# Nguyen_Ly.net
KiCad netlist of a schematic drawn in Altium Designer
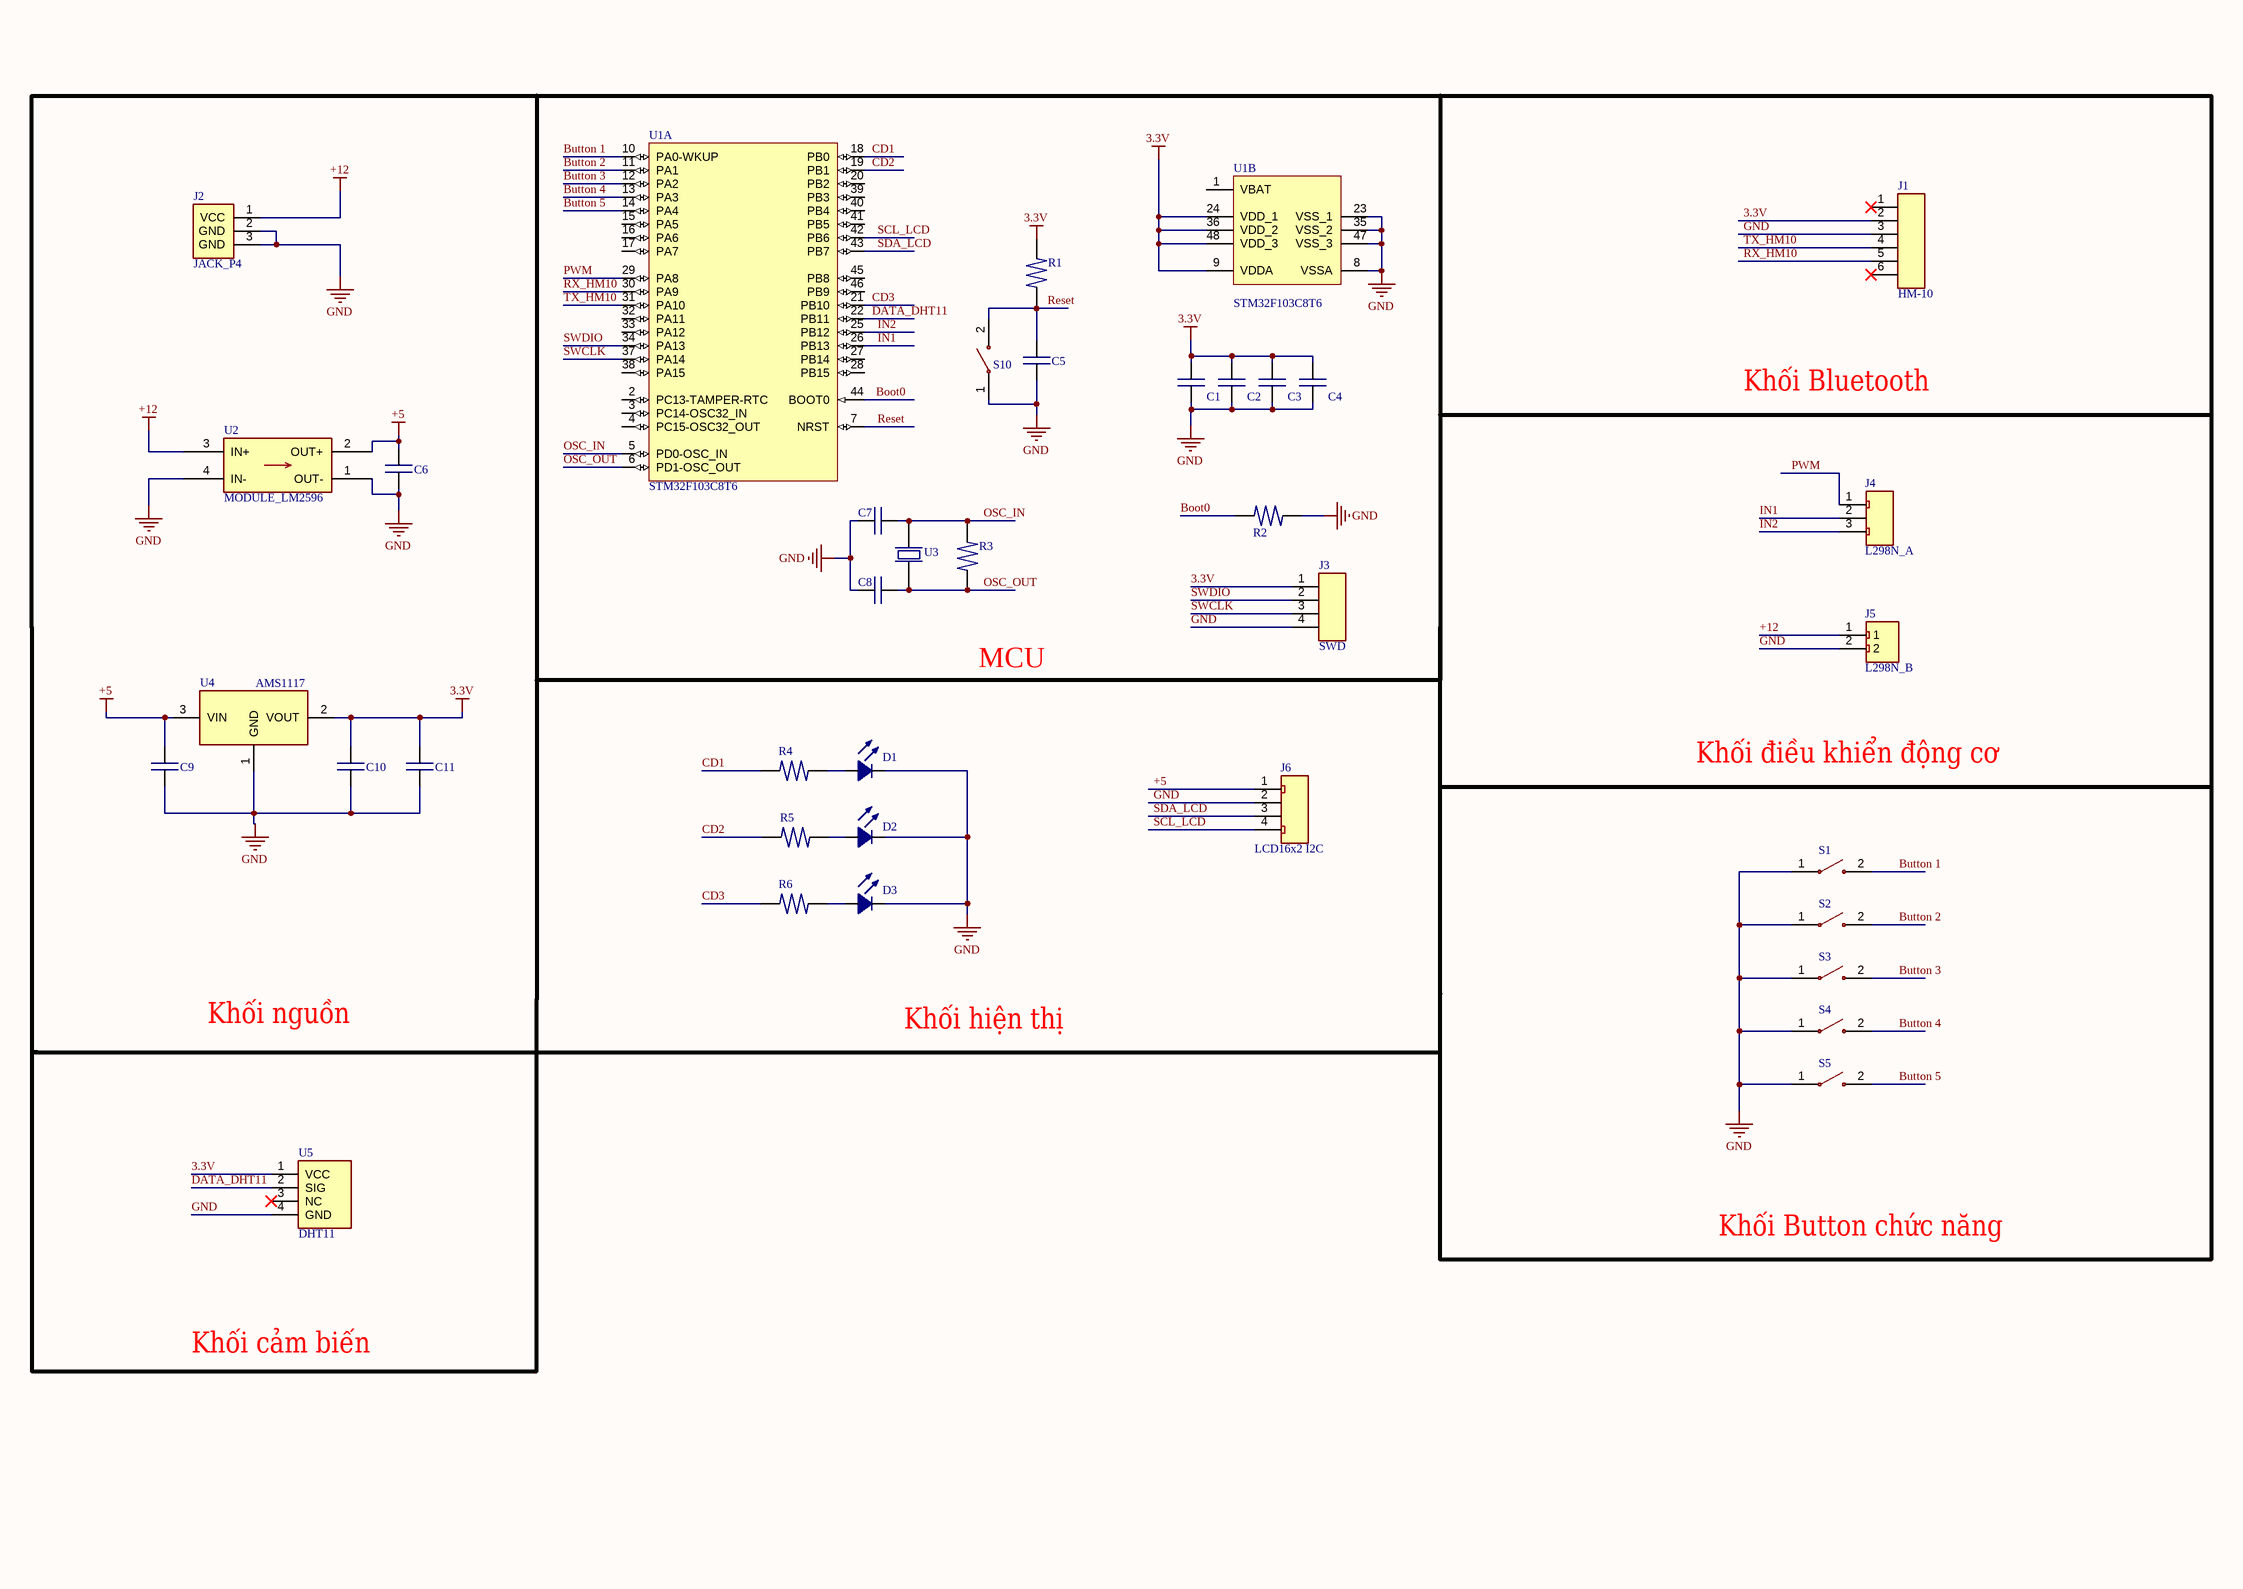
[diagram p0: Nguyen_Ly.SchDoc]

(export (version "E")
  (design (tool "Eeschema 10.0.6"))
  (components
    (comp (ref "C1")
      (value "CAPACITOR 0603")
      (footprint "CAPACITOR 0603")
      (description "Generic Capacitor 0603, 1.6x0.8x0.9mm.")
      (libsource (lib "MyComponents") (part "CAPACITOR 0603"))
    )
    (comp (ref "C2")
      (value "CAPACITOR 0603")
      (footprint "CAPACITOR 0603")
      (description "Generic Capacitor 0603, 1.6x0.8x0.9mm.")
      (libsource (lib "MyComponents") (part "CAPACITOR 0603"))
    )
    (comp (ref "C3")
      (value "CAPACITOR 0603")
      (footprint "CAPACITOR 0603")
      (description "Generic Capacitor 0603, 1.6x0.8x0.9mm.")
      (libsource (lib "MyComponents") (part "CAPACITOR 0603"))
    )
    (comp (ref "C4")
      (value "CAPACITOR 0603")
      (footprint "CAPACITOR 0603")
      (description "Generic Capacitor 0603, 1.6x0.8x0.9mm.")
      (libsource (lib "MyComponents") (part "CAPACITOR 0603"))
    )
    (comp (ref "C5")
      (value "CAPCITOR 104")
      (footprint "CAPACITOR 104")
      (description "Ceramic Capacitor 104, 3mm.")
      (libsource (lib "MyComponents") (part "CAPACITOR 104"))
    )
    (comp (ref "C6")
      (value "CAPCITOR 104")
      (footprint "CAPACITOR 104")
      (description "Ceramic Capacitor 104, 3mm.")
      (libsource (lib "MyComponents") (part "CAPACITOR 104"))
    )
    (comp (ref "C7")
      (value "CAPACITOR 0603")
      (footprint "CAPACITOR 0603")
      (description "Generic Capacitor 0603, 1.6x0.8x0.9mm.")
      (libsource (lib "MyComponents") (part "CAPACITOR 0603"))
    )
    (comp (ref "C8")
      (value "CAPACITOR 0603")
      (footprint "CAPACITOR 0603")
      (description "Generic Capacitor 0603, 1.6x0.8x0.9mm.")
      (libsource (lib "MyComponents") (part "CAPACITOR 0603"))
    )
    (comp (ref "C9")
      (value "CAPACITOR 0603")
      (footprint "CAPACITOR 0603")
      (description "Generic Capacitor 0603, 1.6x0.8x0.9mm.")
      (libsource (lib "MyComponents") (part "CAPACITOR 0603"))
    )
    (comp (ref "C10")
      (value "CAPACITOR 0603")
      (footprint "CAPACITOR 0603")
      (description "Generic Capacitor 0603, 1.6x0.8x0.9mm.")
      (libsource (lib "MyComponents") (part "CAPACITOR 0603"))
    )
    (comp (ref "C11")
      (value "CAPACITOR 0603")
      (footprint "CAPACITOR 0603")
      (description "Generic Capacitor 0603, 1.6x0.8x0.9mm.")
      (libsource (lib "MyComponents") (part "CAPACITOR 0603"))
    )
    (comp (ref "D1")
      (value "LED_5mm_GREEN")
      (footprint "LED_5mm_GREEN")
      (description "LED PTH 5mm Green.")
      (libsource (lib "MyComponents") (part "LED_5mm_GREEN"))
    )
    (comp (ref "D2")
      (value "LED_5mm_YELLOW")
      (footprint "LED_5mm_YELLOW")
      (description "LED PTH 5mm Yellow.")
      (libsource (lib "MyComponents") (part "LED_5mm_YELLOW"))
    )
    (comp (ref "D3")
      (value "LED_5mm_RED")
      (footprint "LED_5mm_RED")
      (description "LED PTH 5mm Red.")
      (libsource (lib "MyComponents") (part "LED_5mm_RED"))
    )
    (comp (ref "J1")
      (value "HM-10")
      (footprint "FEMALE-2.54-6P")
      (description "Female Header Connector 2.54mm 6 Pins.")
      (libsource (lib "MyComponents") (part "FEMALE-2.54-6P"))
    )
    (comp (ref "J2")
      (value "JACK_P4")
      (footprint "JACK_P4")
      (description "9V Battery Connector Jack P4.")
      (libsource (lib "MyComponents") (part "JACK_P4"))
    )
    (comp (ref "J3")
      (value "SWD")
      (footprint "MALE-2.54-4P")
      (description "Male Header Connector 2.54mm 4 Pins.")
      (libsource (lib "MyComponents") (part "MALE-2.54-4P"))
    )
    (comp (ref "J4")
      (value "L298N_A")
      (footprint "JST-2.54-3P")
      (description "Female Connector JST 3 Vias, 2.54mm.")
      (libsource (lib "MyComponents") (part "JST-2.54-3P"))
    )
    (comp (ref "J5")
      (value "L298N_B")
      (footprint "BORNE-5.00-2P")
      (description "Borne 2 Vias, Pitch 5mm.")
      (libsource (lib "MyComponents") (part "BORNE-5.00-2P"))
    )
    (comp (ref "J6")
      (value "LCD16x2 I2C")
      (footprint "JST-2.54-4P")
      (description "Female Connector JST 4 Vias, 2.54mm.")
      (libsource (lib "MyComponents") (part "JST-2.54-4P"))
    )
    (comp (ref "R1")
      (value "RESISTOR_9.5mm")
      (footprint "RESISTOR_PTH_9.5mm")
      (description "Generic Resistor 9.5mm.")
      (libsource (lib "MyComponents") (part "RESISTOR_9.5mm"))
    )
    (comp (ref "R2")
      (value "RESISTOR_0603")
      (footprint "RESISTOR_0603")
      (description "Generic Resistor 0603.")
      (libsource (lib "MyComponents") (part "RESISTOR_0603"))
    )
    (comp (ref "R3")
      (value "RESISTOR_0603")
      (footprint "RESISTOR_0603")
      (description "Generic Resistor 0603.")
      (libsource (lib "MyComponents") (part "RESISTOR_0603"))
    )
    (comp (ref "R4")
      (value "RESISTOR_9.5mm")
      (footprint "RESISTOR_PTH_9.5mm")
      (description "Generic Resistor 9.5mm.")
      (libsource (lib "MyComponents") (part "RESISTOR_9.5mm"))
    )
    (comp (ref "R5")
      (value "RESISTOR_9.5mm")
      (footprint "RESISTOR_PTH_9.5mm")
      (description "Generic Resistor 9.5mm.")
      (libsource (lib "MyComponents") (part "RESISTOR_9.5mm"))
    )
    (comp (ref "R6")
      (value "RESISTOR_9.5mm")
      (footprint "RESISTOR_PTH_9.5mm")
      (description "Generic Resistor 9.5mm.")
      (libsource (lib "MyComponents") (part "RESISTOR_9.5mm"))
    )
    (comp (ref "S1")
      (value "PUSH_BUTTON_6X6")
      (footprint "PUSH_BUTTON_6X6")
      (description "Push Button Tactile Switch PTH 4 Pins 6x6mm.")
      (libsource (lib "") (part "PUSH_BUTTON_6X6_1"))
    )
    (comp (ref "S2")
      (value "PUSH_BUTTON_6X6")
      (footprint "PUSH_BUTTON_6X6")
      (description "Push Button Tactile Switch PTH 4 Pins 6x6mm.")
      (libsource (lib "") (part "PUSH_BUTTON_6X6_1"))
    )
    (comp (ref "S3")
      (value "PUSH_BUTTON_6X6")
      (footprint "PUSH_BUTTON_6X6")
      (description "Push Button Tactile Switch PTH 4 Pins 6x6mm.")
      (libsource (lib "") (part "PUSH_BUTTON_6X6_1"))
    )
    (comp (ref "S4")
      (value "PUSH_BUTTON_6X6")
      (footprint "PUSH_BUTTON_6X6")
      (description "Push Button Tactile Switch PTH 4 Pins 6x6mm.")
      (libsource (lib "") (part "PUSH_BUTTON_6X6_1"))
    )
    (comp (ref "S5")
      (value "PUSH_BUTTON_6X6")
      (footprint "PUSH_BUTTON_6X6")
      (description "Push Button Tactile Switch PTH 4 Pins 6x6mm.")
      (libsource (lib "") (part "PUSH_BUTTON_6X6_1"))
    )
    (comp (ref "S10")
      (value "PUSH_BUTTON_6X6")
      (footprint "PUSH_BUTTON_6X6")
      (description "Push Button Tactile Switch PTH 4 Pins 6x6mm.")
      (libsource (lib "MyComponents") (part "PUSH_BUTTON_6X6"))
    )
    (comp (ref "U1")
      (value "STM32F103C8T6")
      (footprint "STM-LQFP48_N")
      (libsource (lib "STMicroelectronics STM32 F1") (part "STM32F103C8T6"))
    )
    (comp (ref "U2")
      (value "MODULE_LM2596")
      (footprint "MODULE_LM2596")
      (description "MODULE BUCK STEP DOWN 3A 43x20mm")
      (libsource (lib "MyComponents") (part "MODULE_LM2596"))
    )
    (comp (ref "U3")
      (value "CRISTAL_16Mhz")
      (footprint "CRISTAL_16Mhz_SMD")
      (description "CRYSTAL 16MHZ, PTH and SMD")
      (libsource (lib "MyComponents") (part "CRISTAL_16Mhz"))
    )
    (comp (ref "U4")
      (value "AMS1117")
      (footprint "AMS1117")
      (description "IC REG LINEAR 1A SOT-89-3L")
      (libsource (lib "MyComponents") (part "AMS1117"))
    )
    (comp (ref "U5")
      (value "DHT11")
      (footprint "DHT11")
      (description "SENSOR HUMIDITY/TEMPERATURE")
      (libsource (lib "MyComponents") (part "DHT11"))
    )
  )
  (nets
    (net (code "1") (name "+5") (class "Default")
      (node (ref "C6") (pin "2") (pinfunction "2_2") (pintype "passive"))
      (node (ref "C9") (pin "2") (pinfunction "2_2") (pintype "passive"))
      (node (ref "J6") (pin "1") (pintype "passive"))
      (node (ref "U2") (pin "2") (pinfunction "OUT+_2") (pintype "passive"))
      (node (ref "U4") (pin "3") (pinfunction "VIN_3") (pintype "passive"))
    )
    (net (code "2") (name "+12") (class "Default")
      (node (ref "J2") (pin "1") (pinfunction "VCC_1") (pintype "passive"))
      (node (ref "J5") (pin "1") (pinfunction "1_1") (pintype "passive"))
      (node (ref "U2") (pin "3") (pinfunction "IN+_3") (pintype "passive"))
    )
    (net (code "3") (name "/Boot0") (class "Default")
      (node (ref "R2") (pin "2") (pinfunction "2_2") (pintype "passive"))
      (node (ref "U1") (pin "44") (pinfunction "BOOT0_44") (pintype "input"))
    )
    (net (code "4") (name "/Button 1") (class "Default")
      (node (ref "S1") (pin "2") (pinfunction "2_2") (pintype "passive"))
      (node (ref "U1") (pin "10") (pinfunction "PA0-WKUP_10") (pintype "bidirectional"))
    )
    (net (code "5") (name "/Button 2") (class "Default")
      (node (ref "S2") (pin "2") (pinfunction "2_2") (pintype "passive"))
      (node (ref "U1") (pin "11") (pinfunction "PA1_11") (pintype "bidirectional"))
    )
    (net (code "6") (name "/Button 3") (class "Default")
      (node (ref "S3") (pin "2") (pinfunction "2_2") (pintype "passive"))
      (node (ref "U1") (pin "12") (pinfunction "PA2_12") (pintype "bidirectional"))
    )
    (net (code "7") (name "/Button 4") (class "Default")
      (node (ref "S4") (pin "2") (pinfunction "2_2") (pintype "passive"))
      (node (ref "U1") (pin "13") (pinfunction "PA3_13") (pintype "bidirectional"))
    )
    (net (code "8") (name "/Button 5") (class "Default")
      (node (ref "S5") (pin "2") (pinfunction "2_2") (pintype "passive"))
      (node (ref "U1") (pin "14") (pinfunction "PA4_14") (pintype "bidirectional"))
    )
    (net (code "9") (name "/CD1") (class "Default")
      (node (ref "R4") (pin "1") (pinfunction "1_1") (pintype "passive"))
      (node (ref "U1") (pin "18") (pinfunction "PB0_18") (pintype "bidirectional"))
    )
    (net (code "10") (name "/CD2") (class "Default")
      (node (ref "R5") (pin "1") (pinfunction "1_1") (pintype "passive"))
      (node (ref "U1") (pin "19") (pinfunction "PB1_19") (pintype "bidirectional"))
    )
    (net (code "11") (name "/CD3") (class "Default")
      (node (ref "R6") (pin "1") (pinfunction "1_1") (pintype "passive"))
      (node (ref "U1") (pin "21") (pinfunction "PB10_21") (pintype "bidirectional"))
    )
    (net (code "12") (name "/DATA_DHT11") (class "Default")
      (node (ref "U1") (pin "22") (pinfunction "PB11_22") (pintype "bidirectional"))
      (node (ref "U5") (pin "2") (pinfunction "SIG_2") (pintype "passive"))
    )
    (net (code "13") (name "/IN1") (class "Default")
      (node (ref "J4") (pin "2") (pintype "passive"))
      (node (ref "U1") (pin "26") (pinfunction "PB13_26") (pintype "bidirectional"))
    )
    (net (code "14") (name "/IN2") (class "Default")
      (node (ref "J4") (pin "3") (pintype "passive"))
      (node (ref "U1") (pin "25") (pinfunction "PB12_25") (pintype "bidirectional"))
    )
    (net (code "15") (name "/OSC_IN") (class "Default")
      (node (ref "C7") (pin "2") (pinfunction "2_2") (pintype "passive"))
      (node (ref "R3") (pin "2") (pinfunction "2_2") (pintype "passive"))
      (node (ref "U1") (pin "5") (pinfunction "PD0-OSC_IN_5") (pintype "bidirectional"))
      (node (ref "U3") (pin "2") (pinfunction "2_2") (pintype "power_in"))
    )
    (net (code "16") (name "/OSC_OUT") (class "Default")
      (node (ref "C8") (pin "2") (pinfunction "2_2") (pintype "passive"))
      (node (ref "R3") (pin "1") (pinfunction "1_1") (pintype "passive"))
      (node (ref "U1") (pin "6") (pinfunction "PD1-OSC_OUT_6") (pintype "bidirectional"))
      (node (ref "U3") (pin "1") (pinfunction "1_1") (pintype "power_in"))
    )
    (net (code "17") (name "/PWM") (class "Default")
      (node (ref "J4") (pin "1") (pintype "passive"))
      (node (ref "U1") (pin "29") (pinfunction "PA8_29") (pintype "bidirectional"))
    )
    (net (code "18") (name "/RX_HM10") (class "Default")
      (node (ref "J1") (pin "5") (pintype "passive"))
      (node (ref "U1") (pin "30") (pinfunction "PA9_30") (pintype "bidirectional"))
    )
    (net (code "19") (name "/Reset") (class "Default")
      (node (ref "C5") (pin "2") (pinfunction "2_2") (pintype "passive"))
      (node (ref "R1") (pin "1") (pinfunction "1_1") (pintype "passive"))
      (node (ref "S10") (pin "2") (pinfunction "2_2") (pintype "passive"))
      (node (ref "U1") (pin "7") (pinfunction "NRST_7") (pintype "bidirectional"))
    )
    (net (code "20") (name "/SCL_LCD") (class "Default")
      (node (ref "J6") (pin "4") (pintype "passive"))
      (node (ref "U1") (pin "42") (pinfunction "PB6_42") (pintype "bidirectional"))
    )
    (net (code "21") (name "/SDA_LCD") (class "Default")
      (node (ref "J6") (pin "3") (pintype "passive"))
      (node (ref "U1") (pin "43") (pinfunction "PB7_43") (pintype "bidirectional"))
    )
    (net (code "22") (name "/SWCLK") (class "Default")
      (node (ref "J3") (pin "3") (pintype "passive"))
      (node (ref "U1") (pin "37") (pinfunction "PA14_37") (pintype "bidirectional"))
    )
    (net (code "23") (name "/SWDIO") (class "Default")
      (node (ref "J3") (pin "2") (pintype "passive"))
      (node (ref "U1") (pin "34") (pinfunction "PA13_34") (pintype "bidirectional"))
    )
    (net (code "24") (name "/TX_HM10") (class "Default")
      (node (ref "J1") (pin "4") (pintype "passive"))
      (node (ref "U1") (pin "31") (pinfunction "PA10_31") (pintype "bidirectional"))
    )
    (net (code "25") (name "3.3V") (class "Default")
      (node (ref "C1") (pin "2") (pinfunction "2_2") (pintype "passive"))
      (node (ref "C10") (pin "2") (pinfunction "2_2") (pintype "passive"))
      (node (ref "C11") (pin "2") (pinfunction "2_2") (pintype "passive"))
      (node (ref "C2") (pin "2") (pinfunction "2_2") (pintype "passive"))
      (node (ref "C3") (pin "2") (pinfunction "2_2") (pintype "passive"))
      (node (ref "C4") (pin "2") (pinfunction "2_2") (pintype "passive"))
      (node (ref "J1") (pin "2") (pintype "passive"))
      (node (ref "J3") (pin "1") (pintype "passive"))
      (node (ref "R1") (pin "2") (pinfunction "2_2") (pintype "passive"))
      (node (ref "U1") (pin "24") (pinfunction "VDD_1_24") (pintype "power_in"))
      (node (ref "U1") (pin "36") (pinfunction "VDD_2_36") (pintype "power_in"))
      (node (ref "U1") (pin "48") (pinfunction "VDD_3_48") (pintype "power_in"))
      (node (ref "U1") (pin "9") (pinfunction "VDDA_9") (pintype "power_in"))
      (node (ref "U4") (pin "2") (pinfunction "VOUT_2") (pintype "passive"))
      (node (ref "U5") (pin "1") (pinfunction "VCC_1") (pintype "passive"))
    )
    (net (code "26") (name "GND") (class "Default")
      (node (ref "C1") (pin "1") (pinfunction "1_1") (pintype "passive"))
      (node (ref "C10") (pin "1") (pinfunction "1_1") (pintype "passive"))
      (node (ref "C11") (pin "1") (pinfunction "1_1") (pintype "passive"))
      (node (ref "C2") (pin "1") (pinfunction "1_1") (pintype "passive"))
      (node (ref "C3") (pin "1") (pinfunction "1_1") (pintype "passive"))
      (node (ref "C4") (pin "1") (pinfunction "1_1") (pintype "passive"))
      (node (ref "C5") (pin "1") (pinfunction "1_1") (pintype "passive"))
      (node (ref "C6") (pin "1") (pinfunction "1_1") (pintype "passive"))
      (node (ref "C7") (pin "1") (pinfunction "1_1") (pintype "passive"))
      (node (ref "C8") (pin "1") (pinfunction "1_1") (pintype "passive"))
      (node (ref "C9") (pin "1") (pinfunction "1_1") (pintype "passive"))
      (node (ref "D1") (pin "2") (pinfunction "2_2") (pintype "passive"))
      (node (ref "D2") (pin "2") (pinfunction "2_2") (pintype "passive"))
      (node (ref "D3") (pin "2") (pinfunction "2_2") (pintype "passive"))
      (node (ref "J1") (pin "3") (pintype "passive"))
      (node (ref "J2") (pin "2") (pinfunction "GND_2") (pintype "passive"))
      (node (ref "J2") (pin "3") (pinfunction "GND_3") (pintype "passive"))
      (node (ref "J3") (pin "4") (pintype "passive"))
      (node (ref "J5") (pin "2") (pinfunction "2_2") (pintype "passive"))
      (node (ref "J6") (pin "2") (pintype "passive"))
      (node (ref "R2") (pin "1") (pinfunction "1_1") (pintype "passive"))
      (node (ref "S1") (pin "1") (pinfunction "1_1") (pintype "passive"))
      (node (ref "S10") (pin "1") (pinfunction "1_1") (pintype "passive"))
      (node (ref "S2") (pin "1") (pinfunction "1_1") (pintype "passive"))
      (node (ref "S3") (pin "1") (pinfunction "1_1") (pintype "passive"))
      (node (ref "S4") (pin "1") (pinfunction "1_1") (pintype "passive"))
      (node (ref "S5") (pin "1") (pinfunction "1_1") (pintype "passive"))
      (node (ref "U1") (pin "23") (pinfunction "VSS_1_23") (pintype "power_in"))
      (node (ref "U1") (pin "35") (pinfunction "VSS_2_35") (pintype "power_in"))
      (node (ref "U1") (pin "47") (pinfunction "VSS_3_47") (pintype "power_in"))
      (node (ref "U1") (pin "8") (pinfunction "VSSA_8") (pintype "power_in"))
      (node (ref "U2") (pin "1") (pinfunction "OUT-_1") (pintype "passive"))
      (node (ref "U2") (pin "4") (pinfunction "IN-_4") (pintype "passive"))
      (node (ref "U4") (pin "1") (pinfunction "GND_1") (pintype "passive"))
      (node (ref "U5") (pin "4") (pinfunction "GND_4") (pintype "passive"))
    )
    (net (code "27") (name "Net-(D1-Pad1)") (class "Default")
      (node (ref "D1") (pin "1") (pinfunction "1_1") (pintype "passive"))
      (node (ref "R4") (pin "2") (pinfunction "2_2") (pintype "passive"))
    )
    (net (code "28") (name "Net-(D2-Pad1)") (class "Default")
      (node (ref "D2") (pin "1") (pinfunction "1_1") (pintype "passive"))
      (node (ref "R5") (pin "2") (pinfunction "2_2") (pintype "passive"))
    )
    (net (code "29") (name "Net-(D3-Pad1)") (class "Default")
      (node (ref "D3") (pin "1") (pinfunction "1_1") (pintype "passive"))
      (node (ref "R6") (pin "2") (pinfunction "2_2") (pintype "passive"))
    )
    (net (code "30") (name "unconnected-(J1-Pad1)") (class "Default")
      (node (ref "J1") (pin "1") (pintype "passive+no_connect"))
    )
    (net (code "31") (name "unconnected-(J1-Pad6)") (class "Default")
      (node (ref "J1") (pin "6") (pintype "passive+no_connect"))
    )
    (net (code "32") (name "unconnected-(U1A-PA5-Pad15)") (class "Default")
      (node (ref "U1") (pin "15") (pinfunction "PA5_15") (pintype "bidirectional"))
    )
    (net (code "33") (name "unconnected-(U1A-PA6-Pad16)") (class "Default")
      (node (ref "U1") (pin "16") (pinfunction "PA6_16") (pintype "bidirectional"))
    )
    (net (code "34") (name "unconnected-(U1A-PA7-Pad17)") (class "Default")
      (node (ref "U1") (pin "17") (pinfunction "PA7_17") (pintype "bidirectional"))
    )
    (net (code "35") (name "unconnected-(U1A-PA11-Pad32)") (class "Default")
      (node (ref "U1") (pin "32") (pinfunction "PA11_32") (pintype "bidirectional"))
    )
    (net (code "36") (name "unconnected-(U1A-PA12-Pad33)") (class "Default")
      (node (ref "U1") (pin "33") (pinfunction "PA12_33") (pintype "bidirectional"))
    )
    (net (code "37") (name "unconnected-(U1A-PA15-Pad38)") (class "Default")
      (node (ref "U1") (pin "38") (pinfunction "PA15_38") (pintype "bidirectional"))
    )
    (net (code "38") (name "unconnected-(U1A-PB2-Pad20)") (class "Default")
      (node (ref "U1") (pin "20") (pinfunction "PB2_20") (pintype "bidirectional"))
    )
    (net (code "39") (name "unconnected-(U1A-PB3-Pad39)") (class "Default")
      (node (ref "U1") (pin "39") (pinfunction "PB3_39") (pintype "bidirectional"))
    )
    (net (code "40") (name "unconnected-(U1A-PB4-Pad40)") (class "Default")
      (node (ref "U1") (pin "40") (pinfunction "PB4_40") (pintype "bidirectional"))
    )
    (net (code "41") (name "unconnected-(U1A-PB5-Pad41)") (class "Default")
      (node (ref "U1") (pin "41") (pinfunction "PB5_41") (pintype "bidirectional"))
    )
    (net (code "42") (name "unconnected-(U1A-PB8-Pad45)") (class "Default")
      (node (ref "U1") (pin "45") (pinfunction "PB8_45") (pintype "bidirectional"))
    )
    (net (code "43") (name "unconnected-(U1A-PB9-Pad46)") (class "Default")
      (node (ref "U1") (pin "46") (pinfunction "PB9_46") (pintype "bidirectional"))
    )
    (net (code "44") (name "unconnected-(U1A-PB14-Pad27)") (class "Default")
      (node (ref "U1") (pin "27") (pinfunction "PB14_27") (pintype "bidirectional"))
    )
    (net (code "45") (name "unconnected-(U1A-PB15-Pad28)") (class "Default")
      (node (ref "U1") (pin "28") (pinfunction "PB15_28") (pintype "bidirectional"))
    )
    (net (code "46") (name "unconnected-(U1A-PC13-TAMPER-RTC-Pad2)") (class "Default")
      (node (ref "U1") (pin "2") (pinfunction "PC13-TAMPER-RTC_2") (pintype "bidirectional"))
    )
    (net (code "47") (name "unconnected-(U1A-PC14-OSC32_IN-Pad3)") (class "Default")
      (node (ref "U1") (pin "3") (pinfunction "PC14-OSC32_IN_3") (pintype "bidirectional"))
    )
    (net (code "48") (name "unconnected-(U1A-PC15-OSC32_OUT-Pad4)") (class "Default")
      (node (ref "U1") (pin "4") (pinfunction "PC15-OSC32_OUT_4") (pintype "bidirectional"))
    )
    (net (code "49") (name "unconnected-(U1B-VBAT-Pad1)") (class "Default")
      (node (ref "U1") (pin "1") (pinfunction "VBAT_1") (pintype "power_in"))
    )
    (net (code "50") (name "unconnected-(U5-NC-Pad3)") (class "Default")
      (node (ref "U5") (pin "3") (pinfunction "NC_3") (pintype "passive+no_connect"))
    )
  )
)
